# Schametics.net
KiCad netlist of a schematic drawn in EAGLE
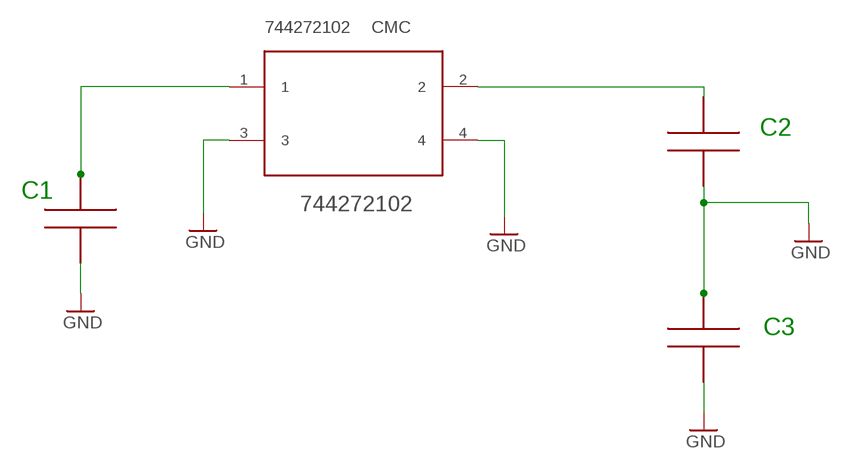
[diagram p0: schematic, sheet 1]

(export (version "E")
  (design (tool "Eeschema 10.0.6"))
  (components
    (comp (ref "744272102")
      (value "CHOKE")
      (footprint "eagle-import:CHOKE")
      (libsource (lib "eagle-import") (part "CHOKE"))
    )
    (comp (ref "U$1")
      (value "1500pF")
      (footprint "eagle-import:FGJGFN")
      (libsource (lib "eagle-import") (part "CAPA1210"))
    )
    (comp (ref "U$2")
      (value "CAPA1210")
      (footprint "eagle-import:FGJGFN")
      (libsource (lib "eagle-import") (part "CAPA1210"))
    )
    (comp (ref "U$3")
      (value "CAPA1210")
      (footprint "eagle-import:FGJGFN")
      (libsource (lib "eagle-import") (part "CAPA1210"))
    )
  )
  (nets
    (net (code "1") (name "GND") (class "Default")
      (node (ref "744272102") (pin "3") (pinfunction "3_3") (pintype "passive"))
      (node (ref "744272102") (pin "4") (pinfunction "4_4") (pintype "passive"))
      (node (ref "U$1") (pin "1") (pinfunction "1_1") (pintype "passive"))
      (node (ref "U$2") (pin "1") (pinfunction "1_1") (pintype "passive"))
      (node (ref "U$3") (pin "1") (pinfunction "1_1") (pintype "passive"))
      (node (ref "U$3") (pin "2") (pinfunction "2_2") (pintype "passive"))
    )
    (net (code "2") (name "Net-(744272102-Pad1)") (class "Default")
      (node (ref "744272102") (pin "1") (pinfunction "1_1") (pintype "passive"))
      (node (ref "U$1") (pin "2") (pinfunction "2_2") (pintype "passive"))
    )
    (net (code "3") (name "Net-(744272102-Pad2)") (class "Default")
      (node (ref "744272102") (pin "2") (pinfunction "2_2") (pintype "passive"))
      (node (ref "U$2") (pin "2") (pinfunction "2_2") (pintype "passive"))
    )
  )
)
